# I2CRJ45.net
KiCad netlist of a schematic drawn in EAGLE
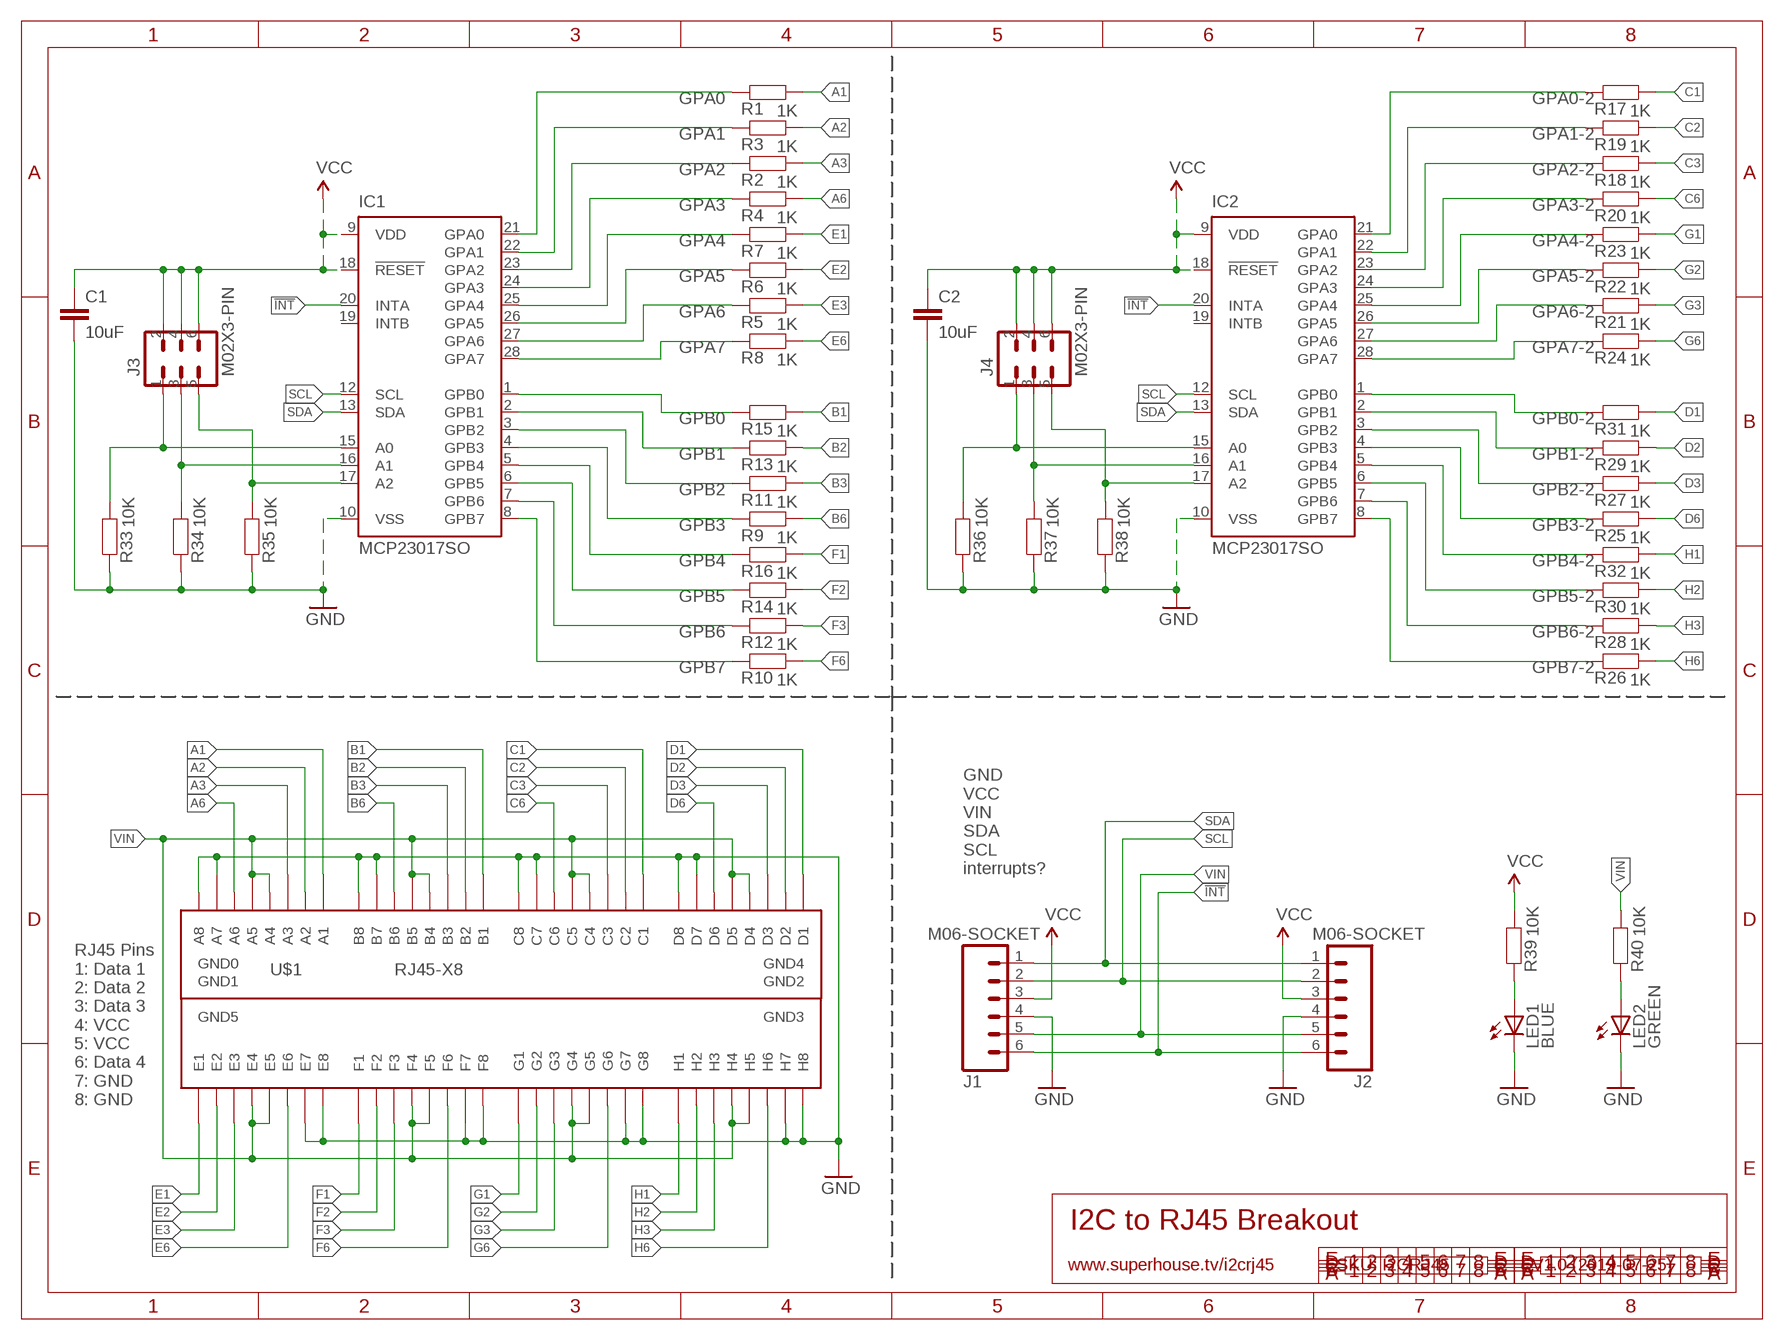
[diagram p0: schematic, sheet 1]

(export (version "E")
  (design (tool "Eeschema 10.0.6"))
  (components
    (comp (ref "C1")
      (value "10uF")
      (footprint "eagle-import:C0805")
      (libsource (lib "eagle-import") (part "CAP0805"))
    )
    (comp (ref "C2")
      (value "10uF")
      (footprint "eagle-import:C0805")
      (libsource (lib "eagle-import") (part "CAP0805"))
    )
    (comp (ref "IC1")
      (value "MCP23017SO")
      (footprint "eagle-import:SO28W")
      (libsource (lib "eagle-import") (part "MCP23017SO"))
    )
    (comp (ref "IC2")
      (value "MCP23017SO")
      (footprint "eagle-import:SO28W")
      (libsource (lib "eagle-import") (part "MCP23017SO"))
    )
    (comp (ref "J1")
      (value "M06-SOCKET")
      (footprint "eagle-import:1X06-S")
      (libsource (lib "eagle-import") (part "M06-SOCKET"))
    )
    (comp (ref "J2")
      (value "M06-SOCKET")
      (footprint "eagle-import:1X06-S")
      (libsource (lib "eagle-import") (part "M06-SOCKET"))
    )
    (comp (ref "J3")
      (value "M02X3-PIN")
      (footprint "eagle-import:2X03-P")
      (libsource (lib "eagle-import") (part "M02X3-PIN"))
    )
    (comp (ref "J4")
      (value "M02X3-PIN")
      (footprint "eagle-import:2X03-P")
      (libsource (lib "eagle-import") (part "M02X3-PIN"))
    )
    (comp (ref "LED1")
      (value "BLUE")
      (footprint "eagle-import:LED-0603")
      (libsource (lib "eagle-import") (part "LED0603"))
    )
    (comp (ref "LED2")
      (value "GREEN")
      (footprint "eagle-import:LED-0603")
      (libsource (lib "eagle-import") (part "LED0603"))
    )
    (comp (ref "R1")
      (value "1K")
      (footprint "eagle-import:R0603")
      (libsource (lib "eagle-import") (part "RESISTOR0603"))
    )
    (comp (ref "R2")
      (value "1K")
      (footprint "eagle-import:R0603")
      (libsource (lib "eagle-import") (part "RESISTOR0603"))
    )
    (comp (ref "R3")
      (value "1K")
      (footprint "eagle-import:R0603")
      (libsource (lib "eagle-import") (part "RESISTOR0603"))
    )
    (comp (ref "R4")
      (value "1K")
      (footprint "eagle-import:R0603")
      (libsource (lib "eagle-import") (part "RESISTOR0603"))
    )
    (comp (ref "R5")
      (value "1K")
      (footprint "eagle-import:R0603")
      (libsource (lib "eagle-import") (part "RESISTOR0603"))
    )
    (comp (ref "R6")
      (value "1K")
      (footprint "eagle-import:R0603")
      (libsource (lib "eagle-import") (part "RESISTOR0603"))
    )
    (comp (ref "R7")
      (value "1K")
      (footprint "eagle-import:R0603")
      (libsource (lib "eagle-import") (part "RESISTOR0603"))
    )
    (comp (ref "R8")
      (value "1K")
      (footprint "eagle-import:R0603")
      (libsource (lib "eagle-import") (part "RESISTOR0603"))
    )
    (comp (ref "R9")
      (value "1K")
      (footprint "eagle-import:R0603")
      (libsource (lib "eagle-import") (part "RESISTOR0603"))
    )
    (comp (ref "R10")
      (value "1K")
      (footprint "eagle-import:R0603")
      (libsource (lib "eagle-import") (part "RESISTOR0603"))
    )
    (comp (ref "R11")
      (value "1K")
      (footprint "eagle-import:R0603")
      (libsource (lib "eagle-import") (part "RESISTOR0603"))
    )
    (comp (ref "R12")
      (value "1K")
      (footprint "eagle-import:R0603")
      (libsource (lib "eagle-import") (part "RESISTOR0603"))
    )
    (comp (ref "R13")
      (value "1K")
      (footprint "eagle-import:R0603")
      (libsource (lib "eagle-import") (part "RESISTOR0603"))
    )
    (comp (ref "R14")
      (value "1K")
      (footprint "eagle-import:R0603")
      (libsource (lib "eagle-import") (part "RESISTOR0603"))
    )
    (comp (ref "R15")
      (value "1K")
      (footprint "eagle-import:R0603")
      (libsource (lib "eagle-import") (part "RESISTOR0603"))
    )
    (comp (ref "R16")
      (value "1K")
      (footprint "eagle-import:R0603")
      (libsource (lib "eagle-import") (part "RESISTOR0603"))
    )
    (comp (ref "R17")
      (value "1K")
      (footprint "eagle-import:R0603")
      (libsource (lib "eagle-import") (part "RESISTOR0603"))
    )
    (comp (ref "R18")
      (value "1K")
      (footprint "eagle-import:R0603")
      (libsource (lib "eagle-import") (part "RESISTOR0603"))
    )
    (comp (ref "R19")
      (value "1K")
      (footprint "eagle-import:R0603")
      (libsource (lib "eagle-import") (part "RESISTOR0603"))
    )
    (comp (ref "R20")
      (value "1K")
      (footprint "eagle-import:R0603")
      (libsource (lib "eagle-import") (part "RESISTOR0603"))
    )
    (comp (ref "R21")
      (value "1K")
      (footprint "eagle-import:R0603")
      (libsource (lib "eagle-import") (part "RESISTOR0603"))
    )
    (comp (ref "R22")
      (value "1K")
      (footprint "eagle-import:R0603")
      (libsource (lib "eagle-import") (part "RESISTOR0603"))
    )
    (comp (ref "R23")
      (value "1K")
      (footprint "eagle-import:R0603")
      (libsource (lib "eagle-import") (part "RESISTOR0603"))
    )
    (comp (ref "R24")
      (value "1K")
      (footprint "eagle-import:R0603")
      (libsource (lib "eagle-import") (part "RESISTOR0603"))
    )
    (comp (ref "R25")
      (value "1K")
      (footprint "eagle-import:R0603")
      (libsource (lib "eagle-import") (part "RESISTOR0603"))
    )
    (comp (ref "R26")
      (value "1K")
      (footprint "eagle-import:R0603")
      (libsource (lib "eagle-import") (part "RESISTOR0603"))
    )
    (comp (ref "R27")
      (value "1K")
      (footprint "eagle-import:R0603")
      (libsource (lib "eagle-import") (part "RESISTOR0603"))
    )
    (comp (ref "R28")
      (value "1K")
      (footprint "eagle-import:R0603")
      (libsource (lib "eagle-import") (part "RESISTOR0603"))
    )
    (comp (ref "R29")
      (value "1K")
      (footprint "eagle-import:R0603")
      (libsource (lib "eagle-import") (part "RESISTOR0603"))
    )
    (comp (ref "R30")
      (value "1K")
      (footprint "eagle-import:R0603")
      (libsource (lib "eagle-import") (part "RESISTOR0603"))
    )
    (comp (ref "R31")
      (value "1K")
      (footprint "eagle-import:R0603")
      (libsource (lib "eagle-import") (part "RESISTOR0603"))
    )
    (comp (ref "R32")
      (value "1K")
      (footprint "eagle-import:R0603")
      (libsource (lib "eagle-import") (part "RESISTOR0603"))
    )
    (comp (ref "R33")
      (value "10K")
      (footprint "eagle-import:R0603")
      (libsource (lib "eagle-import") (part "RESISTOR0603"))
    )
    (comp (ref "R34")
      (value "10K")
      (footprint "eagle-import:R0603")
      (libsource (lib "eagle-import") (part "RESISTOR0603"))
    )
    (comp (ref "R35")
      (value "10K")
      (footprint "eagle-import:R0603")
      (libsource (lib "eagle-import") (part "RESISTOR0603"))
    )
    (comp (ref "R36")
      (value "10K")
      (footprint "eagle-import:R0603")
      (libsource (lib "eagle-import") (part "RESISTOR0603"))
    )
    (comp (ref "R37")
      (value "10K")
      (footprint "eagle-import:R0603")
      (libsource (lib "eagle-import") (part "RESISTOR0603"))
    )
    (comp (ref "R38")
      (value "10K")
      (footprint "eagle-import:R0603")
      (libsource (lib "eagle-import") (part "RESISTOR0603"))
    )
    (comp (ref "R39")
      (value "10K")
      (footprint "eagle-import:R0603")
      (libsource (lib "eagle-import") (part "RESISTOR0603"))
    )
    (comp (ref "R40")
      (value "10K")
      (footprint "eagle-import:R0603")
      (libsource (lib "eagle-import") (part "RESISTOR0603"))
    )
    (comp (ref "U$1")
      (value "RJ45-X8")
      (footprint "eagle-import:RJ45-2X4")
      (libsource (lib "eagle-import") (part "RJ45-X8"))
    )
  )
  (nets
    (net (code "1") (name "/GND0") (class "Default")
      (node (ref "U$1") (pin "GND0") (pinfunction "GND0_GND0") (pintype "power_in"))
    )
    (net (code "2") (name "/GND1") (class "Default")
      (node (ref "U$1") (pin "GND1") (pinfunction "GND1_GND1") (pintype "power_in"))
    )
    (net (code "3") (name "/GND2") (class "Default")
      (node (ref "U$1") (pin "GND2") (pinfunction "GND2_GND2") (pintype "power_in"))
    )
    (net (code "4") (name "/GND3") (class "Default")
      (node (ref "U$1") (pin "GND3") (pinfunction "GND3_GND3") (pintype "power_in"))
    )
    (net (code "5") (name "/GND4") (class "Default")
      (node (ref "U$1") (pin "GND4") (pinfunction "GND4_GND4") (pintype "power_in"))
    )
    (net (code "6") (name "/GND5") (class "Default")
      (node (ref "U$1") (pin "GND5") (pinfunction "GND5_GND5") (pintype "power_in"))
    )
    (net (code "7") (name "/GPA0") (class "Default")
      (node (ref "IC1") (pin "21") (pinfunction "GPA0_21") (pintype "bidirectional"))
      (node (ref "R1") (pin "1") (pinfunction "1_1") (pintype "passive"))
    )
    (net (code "8") (name "/GPA0-2") (class "Default")
      (node (ref "IC2") (pin "21") (pinfunction "GPA0_21") (pintype "bidirectional"))
      (node (ref "R17") (pin "1") (pinfunction "1_1") (pintype "passive"))
    )
    (net (code "9") (name "/GPA1") (class "Default")
      (node (ref "IC1") (pin "22") (pinfunction "GPA1_22") (pintype "bidirectional"))
      (node (ref "R3") (pin "1") (pinfunction "1_1") (pintype "passive"))
    )
    (net (code "10") (name "/GPA1-2") (class "Default")
      (node (ref "IC2") (pin "22") (pinfunction "GPA1_22") (pintype "bidirectional"))
      (node (ref "R19") (pin "1") (pinfunction "1_1") (pintype "passive"))
    )
    (net (code "11") (name "/GPA2") (class "Default")
      (node (ref "IC1") (pin "23") (pinfunction "GPA2_23") (pintype "bidirectional"))
      (node (ref "R2") (pin "1") (pinfunction "1_1") (pintype "passive"))
    )
    (net (code "12") (name "/GPA2-2") (class "Default")
      (node (ref "IC2") (pin "23") (pinfunction "GPA2_23") (pintype "bidirectional"))
      (node (ref "R18") (pin "1") (pinfunction "1_1") (pintype "passive"))
    )
    (net (code "13") (name "/GPA3") (class "Default")
      (node (ref "IC1") (pin "24") (pinfunction "GPA3_24") (pintype "bidirectional"))
      (node (ref "R4") (pin "1") (pinfunction "1_1") (pintype "passive"))
    )
    (net (code "14") (name "/GPA3-2") (class "Default")
      (node (ref "IC2") (pin "24") (pinfunction "GPA3_24") (pintype "bidirectional"))
      (node (ref "R20") (pin "1") (pinfunction "1_1") (pintype "passive"))
    )
    (net (code "15") (name "/GPA4") (class "Default")
      (node (ref "IC1") (pin "25") (pinfunction "GPA4_25") (pintype "bidirectional"))
      (node (ref "R7") (pin "1") (pinfunction "1_1") (pintype "passive"))
    )
    (net (code "16") (name "/GPA4-2") (class "Default")
      (node (ref "IC2") (pin "25") (pinfunction "GPA4_25") (pintype "bidirectional"))
      (node (ref "R23") (pin "1") (pinfunction "1_1") (pintype "passive"))
    )
    (net (code "17") (name "/GPA5") (class "Default")
      (node (ref "IC1") (pin "26") (pinfunction "GPA5_26") (pintype "bidirectional"))
      (node (ref "R6") (pin "1") (pinfunction "1_1") (pintype "passive"))
    )
    (net (code "18") (name "/GPA5-2") (class "Default")
      (node (ref "IC2") (pin "26") (pinfunction "GPA5_26") (pintype "bidirectional"))
      (node (ref "R22") (pin "1") (pinfunction "1_1") (pintype "passive"))
    )
    (net (code "19") (name "/GPA6") (class "Default")
      (node (ref "IC1") (pin "27") (pinfunction "GPA6_27") (pintype "bidirectional"))
      (node (ref "R5") (pin "1") (pinfunction "1_1") (pintype "passive"))
    )
    (net (code "20") (name "/GPA6-2") (class "Default")
      (node (ref "IC2") (pin "27") (pinfunction "GPA6_27") (pintype "bidirectional"))
      (node (ref "R21") (pin "1") (pinfunction "1_1") (pintype "passive"))
    )
    (net (code "21") (name "/GPA7") (class "Default")
      (node (ref "IC1") (pin "28") (pinfunction "GPA7_28") (pintype "bidirectional"))
      (node (ref "R8") (pin "1") (pinfunction "1_1") (pintype "passive"))
    )
    (net (code "22") (name "/GPA7-2") (class "Default")
      (node (ref "IC2") (pin "28") (pinfunction "GPA7_28") (pintype "bidirectional"))
      (node (ref "R24") (pin "1") (pinfunction "1_1") (pintype "passive"))
    )
    (net (code "23") (name "/GPB0") (class "Default")
      (node (ref "IC1") (pin "1") (pinfunction "GPB0_1") (pintype "bidirectional"))
      (node (ref "R15") (pin "1") (pinfunction "1_1") (pintype "passive"))
    )
    (net (code "24") (name "/GPB0-2") (class "Default")
      (node (ref "IC2") (pin "1") (pinfunction "GPB0_1") (pintype "bidirectional"))
      (node (ref "R31") (pin "1") (pinfunction "1_1") (pintype "passive"))
    )
    (net (code "25") (name "/GPB1") (class "Default")
      (node (ref "IC1") (pin "2") (pinfunction "GPB1_2") (pintype "bidirectional"))
      (node (ref "R13") (pin "1") (pinfunction "1_1") (pintype "passive"))
    )
    (net (code "26") (name "/GPB1-2") (class "Default")
      (node (ref "IC2") (pin "2") (pinfunction "GPB1_2") (pintype "bidirectional"))
      (node (ref "R29") (pin "1") (pinfunction "1_1") (pintype "passive"))
    )
    (net (code "27") (name "/GPB2") (class "Default")
      (node (ref "IC1") (pin "3") (pinfunction "GPB2_3") (pintype "bidirectional"))
      (node (ref "R11") (pin "1") (pinfunction "1_1") (pintype "passive"))
    )
    (net (code "28") (name "/GPB2-2") (class "Default")
      (node (ref "IC2") (pin "3") (pinfunction "GPB2_3") (pintype "bidirectional"))
      (node (ref "R27") (pin "1") (pinfunction "1_1") (pintype "passive"))
    )
    (net (code "29") (name "/GPB3") (class "Default")
      (node (ref "IC1") (pin "4") (pinfunction "GPB3_4") (pintype "bidirectional"))
      (node (ref "R9") (pin "1") (pinfunction "1_1") (pintype "passive"))
    )
    (net (code "30") (name "/GPB3-2") (class "Default")
      (node (ref "IC2") (pin "4") (pinfunction "GPB3_4") (pintype "bidirectional"))
      (node (ref "R25") (pin "1") (pinfunction "1_1") (pintype "passive"))
    )
    (net (code "31") (name "/GPB4") (class "Default")
      (node (ref "IC1") (pin "5") (pinfunction "GPB4_5") (pintype "bidirectional"))
      (node (ref "R16") (pin "1") (pinfunction "1_1") (pintype "passive"))
    )
    (net (code "32") (name "/GPB4-2") (class "Default")
      (node (ref "IC2") (pin "5") (pinfunction "GPB4_5") (pintype "bidirectional"))
      (node (ref "R32") (pin "1") (pinfunction "1_1") (pintype "passive"))
    )
    (net (code "33") (name "/GPB5") (class "Default")
      (node (ref "IC1") (pin "6") (pinfunction "GPB5_6") (pintype "bidirectional"))
      (node (ref "R14") (pin "1") (pinfunction "1_1") (pintype "passive"))
    )
    (net (code "34") (name "/GPB5-2") (class "Default")
      (node (ref "IC2") (pin "6") (pinfunction "GPB5_6") (pintype "bidirectional"))
      (node (ref "R30") (pin "1") (pinfunction "1_1") (pintype "passive"))
    )
    (net (code "35") (name "/GPB6") (class "Default")
      (node (ref "IC1") (pin "7") (pinfunction "GPB6_7") (pintype "bidirectional"))
      (node (ref "R12") (pin "1") (pinfunction "1_1") (pintype "passive"))
    )
    (net (code "36") (name "/GPB6-2") (class "Default")
      (node (ref "IC2") (pin "7") (pinfunction "GPB6_7") (pintype "bidirectional"))
      (node (ref "R28") (pin "1") (pinfunction "1_1") (pintype "passive"))
    )
    (net (code "37") (name "/GPB7") (class "Default")
      (node (ref "IC1") (pin "8") (pinfunction "GPB7_8") (pintype "bidirectional"))
      (node (ref "R10") (pin "1") (pinfunction "1_1") (pintype "passive"))
    )
    (net (code "38") (name "/GPB7-2") (class "Default")
      (node (ref "IC2") (pin "8") (pinfunction "GPB7_8") (pintype "bidirectional"))
      (node (ref "R26") (pin "1") (pinfunction "1_1") (pintype "passive"))
    )
    (net (code "39") (name "/~{INT}") (class "Default")
      (node (ref "IC1") (pin "20") (pinfunction "INTA_20") (pintype "output"))
      (node (ref "IC2") (pin "20") (pinfunction "INTA_20") (pintype "output"))
      (node (ref "J1") (pin "6") (pinfunction "6_6") (pintype "passive"))
      (node (ref "J2") (pin "6") (pinfunction "6_6") (pintype "passive"))
    )
    (net (code "40") (name "A1") (class "Default")
      (node (ref "R1") (pin "2") (pinfunction "2_2") (pintype "passive"))
      (node (ref "U$1") (pin "A1") (pinfunction "A1_A1") (pintype "bidirectional"))
    )
    (net (code "41") (name "A2") (class "Default")
      (node (ref "R3") (pin "2") (pinfunction "2_2") (pintype "passive"))
      (node (ref "U$1") (pin "A2") (pinfunction "A2_A2") (pintype "bidirectional"))
    )
    (net (code "42") (name "A3") (class "Default")
      (node (ref "R2") (pin "2") (pinfunction "2_2") (pintype "passive"))
      (node (ref "U$1") (pin "A3") (pinfunction "A3_A3") (pintype "bidirectional"))
    )
    (net (code "43") (name "A6") (class "Default")
      (node (ref "R4") (pin "2") (pinfunction "2_2") (pintype "passive"))
      (node (ref "U$1") (pin "A6") (pinfunction "A6_A6") (pintype "bidirectional"))
    )
    (net (code "44") (name "B1") (class "Default")
      (node (ref "R15") (pin "2") (pinfunction "2_2") (pintype "passive"))
      (node (ref "U$1") (pin "B1") (pinfunction "B1_B1") (pintype "bidirectional"))
    )
    (net (code "45") (name "B2") (class "Default")
      (node (ref "R13") (pin "2") (pinfunction "2_2") (pintype "passive"))
      (node (ref "U$1") (pin "B2") (pinfunction "B2_B2") (pintype "bidirectional"))
    )
    (net (code "46") (name "B3") (class "Default")
      (node (ref "R11") (pin "2") (pinfunction "2_2") (pintype "passive"))
      (node (ref "U$1") (pin "B3") (pinfunction "B3_B3") (pintype "bidirectional"))
    )
    (net (code "47") (name "B6") (class "Default")
      (node (ref "R9") (pin "2") (pinfunction "2_2") (pintype "passive"))
      (node (ref "U$1") (pin "B6") (pinfunction "B6_B6") (pintype "bidirectional"))
    )
    (net (code "48") (name "C1") (class "Default")
      (node (ref "R17") (pin "2") (pinfunction "2_2") (pintype "passive"))
      (node (ref "U$1") (pin "C1") (pinfunction "C1_C1") (pintype "bidirectional"))
    )
    (net (code "49") (name "C2") (class "Default")
      (node (ref "R19") (pin "2") (pinfunction "2_2") (pintype "passive"))
      (node (ref "U$1") (pin "C2") (pinfunction "C2_C2") (pintype "bidirectional"))
    )
    (net (code "50") (name "C3") (class "Default")
      (node (ref "R18") (pin "2") (pinfunction "2_2") (pintype "passive"))
      (node (ref "U$1") (pin "C3") (pinfunction "C3_C3") (pintype "bidirectional"))
    )
    (net (code "51") (name "C6") (class "Default")
      (node (ref "R20") (pin "2") (pinfunction "2_2") (pintype "passive"))
      (node (ref "U$1") (pin "C6") (pinfunction "C6_C6") (pintype "bidirectional"))
    )
    (net (code "52") (name "D1") (class "Default")
      (node (ref "R31") (pin "2") (pinfunction "2_2") (pintype "passive"))
      (node (ref "U$1") (pin "D1") (pinfunction "D1_D1") (pintype "bidirectional"))
    )
    (net (code "53") (name "D2") (class "Default")
      (node (ref "R29") (pin "2") (pinfunction "2_2") (pintype "passive"))
      (node (ref "U$1") (pin "D2") (pinfunction "D2_D2") (pintype "bidirectional"))
    )
    (net (code "54") (name "D3") (class "Default")
      (node (ref "R27") (pin "2") (pinfunction "2_2") (pintype "passive"))
      (node (ref "U$1") (pin "D3") (pinfunction "D3_D3") (pintype "bidirectional"))
    )
    (net (code "55") (name "D6") (class "Default")
      (node (ref "R25") (pin "2") (pinfunction "2_2") (pintype "passive"))
      (node (ref "U$1") (pin "D6") (pinfunction "D6_D6") (pintype "bidirectional"))
    )
    (net (code "56") (name "E1") (class "Default")
      (node (ref "R7") (pin "2") (pinfunction "2_2") (pintype "passive"))
      (node (ref "U$1") (pin "E1") (pinfunction "E1_E1") (pintype "bidirectional"))
    )
    (net (code "57") (name "E2") (class "Default")
      (node (ref "R6") (pin "2") (pinfunction "2_2") (pintype "passive"))
      (node (ref "U$1") (pin "E2") (pinfunction "E2_E2") (pintype "bidirectional"))
    )
    (net (code "58") (name "E3") (class "Default")
      (node (ref "R5") (pin "2") (pinfunction "2_2") (pintype "passive"))
      (node (ref "U$1") (pin "E3") (pinfunction "E3_E3") (pintype "bidirectional"))
    )
    (net (code "59") (name "E6") (class "Default")
      (node (ref "R8") (pin "2") (pinfunction "2_2") (pintype "passive"))
      (node (ref "U$1") (pin "E6") (pinfunction "E6_E6") (pintype "bidirectional"))
    )
    (net (code "60") (name "F1") (class "Default")
      (node (ref "R16") (pin "2") (pinfunction "2_2") (pintype "passive"))
      (node (ref "U$1") (pin "F1") (pinfunction "F1_F1") (pintype "bidirectional"))
    )
    (net (code "61") (name "F2") (class "Default")
      (node (ref "R14") (pin "2") (pinfunction "2_2") (pintype "passive"))
      (node (ref "U$1") (pin "F2") (pinfunction "F2_F2") (pintype "bidirectional"))
    )
    (net (code "62") (name "F3") (class "Default")
      (node (ref "R12") (pin "2") (pinfunction "2_2") (pintype "passive"))
      (node (ref "U$1") (pin "F3") (pinfunction "F3_F3") (pintype "bidirectional"))
    )
    (net (code "63") (name "F6") (class "Default")
      (node (ref "R10") (pin "2") (pinfunction "2_2") (pintype "passive"))
      (node (ref "U$1") (pin "F6") (pinfunction "F6_F6") (pintype "bidirectional"))
    )
    (net (code "64") (name "G1") (class "Default")
      (node (ref "R23") (pin "2") (pinfunction "2_2") (pintype "passive"))
      (node (ref "U$1") (pin "G1") (pinfunction "G1_G1") (pintype "bidirectional"))
    )
    (net (code "65") (name "G2") (class "Default")
      (node (ref "R22") (pin "2") (pinfunction "2_2") (pintype "passive"))
      (node (ref "U$1") (pin "G2") (pinfunction "G2_G2") (pintype "bidirectional"))
    )
    (net (code "66") (name "G3") (class "Default")
      (node (ref "R21") (pin "2") (pinfunction "2_2") (pintype "passive"))
      (node (ref "U$1") (pin "G3") (pinfunction "G3_G3") (pintype "bidirectional"))
    )
    (net (code "67") (name "G6") (class "Default")
      (node (ref "R24") (pin "2") (pinfunction "2_2") (pintype "passive"))
      (node (ref "U$1") (pin "G6") (pinfunction "G6_G6") (pintype "bidirectional"))
    )
    (net (code "68") (name "GND") (class "Default")
      (node (ref "C1") (pin "2") (pinfunction "2_2") (pintype "passive"))
      (node (ref "C2") (pin "2") (pinfunction "2_2") (pintype "passive"))
      (node (ref "IC1") (pin "10") (pinfunction "VSS_10") (pintype "power_in"))
      (node (ref "IC2") (pin "10") (pinfunction "VSS_10") (pintype "power_in"))
      (node (ref "J1") (pin "4") (pinfunction "4_4") (pintype "passive"))
      (node (ref "J2") (pin "4") (pinfunction "4_4") (pintype "passive"))
      (node (ref "LED1") (pin "C") (pinfunction "C_C") (pintype "passive"))
      (node (ref "LED2") (pin "C") (pinfunction "C_C") (pintype "passive"))
      (node (ref "R33") (pin "1") (pinfunction "1_1") (pintype "passive"))
      (node (ref "R34") (pin "1") (pinfunction "1_1") (pintype "passive"))
      (node (ref "R35") (pin "1") (pinfunction "1_1") (pintype "passive"))
      (node (ref "R36") (pin "1") (pinfunction "1_1") (pintype "passive"))
      (node (ref "R37") (pin "1") (pinfunction "1_1") (pintype "passive"))
      (node (ref "R38") (pin "1") (pinfunction "1_1") (pintype "passive"))
      (node (ref "U$1") (pin "A7") (pinfunction "A7_A7") (pintype "bidirectional"))
      (node (ref "U$1") (pin "A8") (pinfunction "A8_A8") (pintype "bidirectional"))
      (node (ref "U$1") (pin "B7") (pinfunction "B7_B7") (pintype "bidirectional"))
      (node (ref "U$1") (pin "B8") (pinfunction "B8_B8") (pintype "bidirectional"))
      (node (ref "U$1") (pin "C7") (pinfunction "C7_C7") (pintype "bidirectional"))
      (node (ref "U$1") (pin "C8") (pinfunction "C8_C8") (pintype "bidirectional"))
      (node (ref "U$1") (pin "D7") (pinfunction "D7_D7") (pintype "bidirectional"))
      (node (ref "U$1") (pin "D8") (pinfunction "D8_D8") (pintype "bidirectional"))
      (node (ref "U$1") (pin "E7") (pinfunction "E7_E7") (pintype "bidirectional"))
      (node (ref "U$1") (pin "E8") (pinfunction "E8_E8") (pintype "bidirectional"))
      (node (ref "U$1") (pin "F7") (pinfunction "F7_F7") (pintype "bidirectional"))
      (node (ref "U$1") (pin "F8") (pinfunction "F8_F8") (pintype "bidirectional"))
      (node (ref "U$1") (pin "G7") (pinfunction "G7_G7") (pintype "bidirectional"))
      (node (ref "U$1") (pin "G8") (pinfunction "G8_G8") (pintype "bidirectional"))
      (node (ref "U$1") (pin "H7") (pinfunction "H7_H7") (pintype "bidirectional"))
      (node (ref "U$1") (pin "H8") (pinfunction "H8_H8") (pintype "bidirectional"))
    )
    (net (code "69") (name "H1") (class "Default")
      (node (ref "R32") (pin "2") (pinfunction "2_2") (pintype "passive"))
      (node (ref "U$1") (pin "H1") (pinfunction "H1_H1") (pintype "bidirectional"))
    )
    (net (code "70") (name "H2") (class "Default")
      (node (ref "R30") (pin "2") (pinfunction "2_2") (pintype "passive"))
      (node (ref "U$1") (pin "H2") (pinfunction "H2_H2") (pintype "bidirectional"))
    )
    (net (code "71") (name "H3") (class "Default")
      (node (ref "R28") (pin "2") (pinfunction "2_2") (pintype "passive"))
      (node (ref "U$1") (pin "H3") (pinfunction "H3_H3") (pintype "bidirectional"))
    )
    (net (code "72") (name "H6") (class "Default")
      (node (ref "R26") (pin "2") (pinfunction "2_2") (pintype "passive"))
      (node (ref "U$1") (pin "H6") (pinfunction "H6_H6") (pintype "bidirectional"))
    )
    (net (code "73") (name "Net-(IC1-A0)") (class "Default")
      (node (ref "IC1") (pin "15") (pinfunction "A0_15") (pintype "input"))
      (node (ref "J3") (pin "1") (pinfunction "1_1") (pintype "passive"))
      (node (ref "R33") (pin "2") (pinfunction "2_2") (pintype "passive"))
    )
    (net (code "74") (name "Net-(IC1-A1)") (class "Default")
      (node (ref "IC1") (pin "16") (pinfunction "A1_16") (pintype "input"))
      (node (ref "J3") (pin "3") (pinfunction "3_3") (pintype "passive"))
      (node (ref "R34") (pin "2") (pinfunction "2_2") (pintype "passive"))
    )
    (net (code "75") (name "Net-(IC1-A2)") (class "Default")
      (node (ref "IC1") (pin "17") (pinfunction "A2_17") (pintype "input"))
      (node (ref "J3") (pin "5") (pinfunction "5_5") (pintype "passive"))
      (node (ref "R35") (pin "2") (pinfunction "2_2") (pintype "passive"))
    )
    (net (code "76") (name "Net-(IC2-A0)") (class "Default")
      (node (ref "IC2") (pin "15") (pinfunction "A0_15") (pintype "input"))
      (node (ref "J4") (pin "1") (pinfunction "1_1") (pintype "passive"))
      (node (ref "R36") (pin "2") (pinfunction "2_2") (pintype "passive"))
    )
    (net (code "77") (name "Net-(IC2-A1)") (class "Default")
      (node (ref "IC2") (pin "16") (pinfunction "A1_16") (pintype "input"))
      (node (ref "J4") (pin "3") (pinfunction "3_3") (pintype "passive"))
      (node (ref "R37") (pin "2") (pinfunction "2_2") (pintype "passive"))
    )
    (net (code "78") (name "Net-(IC2-A2)") (class "Default")
      (node (ref "IC2") (pin "17") (pinfunction "A2_17") (pintype "input"))
      (node (ref "J4") (pin "5") (pinfunction "5_5") (pintype "passive"))
      (node (ref "R38") (pin "2") (pinfunction "2_2") (pintype "passive"))
    )
    (net (code "79") (name "Net-(LED1-PadA)") (class "Default")
      (node (ref "LED1") (pin "A") (pinfunction "A_A") (pintype "passive"))
      (node (ref "R39") (pin "1") (pinfunction "1_1") (pintype "passive"))
    )
    (net (code "80") (name "Net-(LED2-PadA)") (class "Default")
      (node (ref "LED2") (pin "A") (pinfunction "A_A") (pintype "passive"))
      (node (ref "R40") (pin "1") (pinfunction "1_1") (pintype "passive"))
    )
    (net (code "81") (name "SCL") (class "Default")
      (node (ref "IC1") (pin "12") (pinfunction "SCL_12") (pintype "input"))
      (node (ref "IC2") (pin "12") (pinfunction "SCL_12") (pintype "input"))
      (node (ref "J1") (pin "2") (pinfunction "2_2") (pintype "passive"))
      (node (ref "J2") (pin "2") (pinfunction "2_2") (pintype "passive"))
    )
    (net (code "82") (name "SDA") (class "Default")
      (node (ref "IC1") (pin "13") (pinfunction "SDA_13") (pintype "bidirectional"))
      (node (ref "IC2") (pin "13") (pinfunction "SDA_13") (pintype "bidirectional"))
      (node (ref "J1") (pin "1") (pinfunction "1_1") (pintype "passive"))
      (node (ref "J2") (pin "1") (pinfunction "1_1") (pintype "passive"))
    )
    (net (code "83") (name "VCC") (class "Default")
      (node (ref "C1") (pin "1") (pinfunction "1_1") (pintype "passive"))
      (node (ref "C2") (pin "1") (pinfunction "1_1") (pintype "passive"))
      (node (ref "IC1") (pin "18") (pinfunction "~{RESET}_18") (pintype "input"))
      (node (ref "IC1") (pin "9") (pinfunction "VDD_9") (pintype "power_in"))
      (node (ref "IC2") (pin "18") (pinfunction "~{RESET}_18") (pintype "input"))
      (node (ref "IC2") (pin "9") (pinfunction "VDD_9") (pintype "power_in"))
      (node (ref "J1") (pin "3") (pinfunction "3_3") (pintype "passive"))
      (node (ref "J2") (pin "3") (pinfunction "3_3") (pintype "passive"))
      (node (ref "J3") (pin "2") (pinfunction "2_2") (pintype "passive"))
      (node (ref "J3") (pin "4") (pinfunction "4_4") (pintype "passive"))
      (node (ref "J3") (pin "6") (pinfunction "6_6") (pintype "passive"))
      (node (ref "J4") (pin "2") (pinfunction "2_2") (pintype "passive"))
      (node (ref "J4") (pin "4") (pinfunction "4_4") (pintype "passive"))
      (node (ref "J4") (pin "6") (pinfunction "6_6") (pintype "passive"))
      (node (ref "R39") (pin "2") (pinfunction "2_2") (pintype "passive"))
    )
    (net (code "84") (name "VIN") (class "Default")
      (node (ref "J1") (pin "5") (pinfunction "5_5") (pintype "passive"))
      (node (ref "J2") (pin "5") (pinfunction "5_5") (pintype "passive"))
      (node (ref "R40") (pin "2") (pinfunction "2_2") (pintype "passive"))
      (node (ref "U$1") (pin "A4") (pinfunction "A4_A4") (pintype "bidirectional"))
      (node (ref "U$1") (pin "A5") (pinfunction "A5_A5") (pintype "bidirectional"))
      (node (ref "U$1") (pin "B4") (pinfunction "B4_B4") (pintype "bidirectional"))
      (node (ref "U$1") (pin "B5") (pinfunction "B5_B5") (pintype "bidirectional"))
      (node (ref "U$1") (pin "C4") (pinfunction "C4_C4") (pintype "bidirectional"))
      (node (ref "U$1") (pin "C5") (pinfunction "C5_C5") (pintype "bidirectional"))
      (node (ref "U$1") (pin "D4") (pinfunction "D4_D4") (pintype "bidirectional"))
      (node (ref "U$1") (pin "D5") (pinfunction "D5_D5") (pintype "bidirectional"))
      (node (ref "U$1") (pin "E4") (pinfunction "E4_E4") (pintype "bidirectional"))
      (node (ref "U$1") (pin "E5") (pinfunction "E5_E5") (pintype "bidirectional"))
      (node (ref "U$1") (pin "F4") (pinfunction "F4_F4") (pintype "bidirectional"))
      (node (ref "U$1") (pin "F5") (pinfunction "F5_F5") (pintype "bidirectional"))
      (node (ref "U$1") (pin "G4") (pinfunction "G4_G4") (pintype "bidirectional"))
      (node (ref "U$1") (pin "G5") (pinfunction "G5_G5") (pintype "bidirectional"))
      (node (ref "U$1") (pin "H4") (pinfunction "H4_H4") (pintype "bidirectional"))
      (node (ref "U$1") (pin "H5") (pinfunction "H5_H5") (pintype "bidirectional"))
    )
    (net (code "85") (name "unconnected-(IC1-INTB-Pad19)") (class "Default")
      (node (ref "IC1") (pin "19") (pinfunction "INTB_19") (pintype "output"))
    )
    (net (code "86") (name "unconnected-(IC2-INTB-Pad19)") (class "Default")
      (node (ref "IC2") (pin "19") (pinfunction "INTB_19") (pintype "output"))
    )
  )
)
